# Dyno.net
KiCad netlist of a schematic drawn in EAGLE
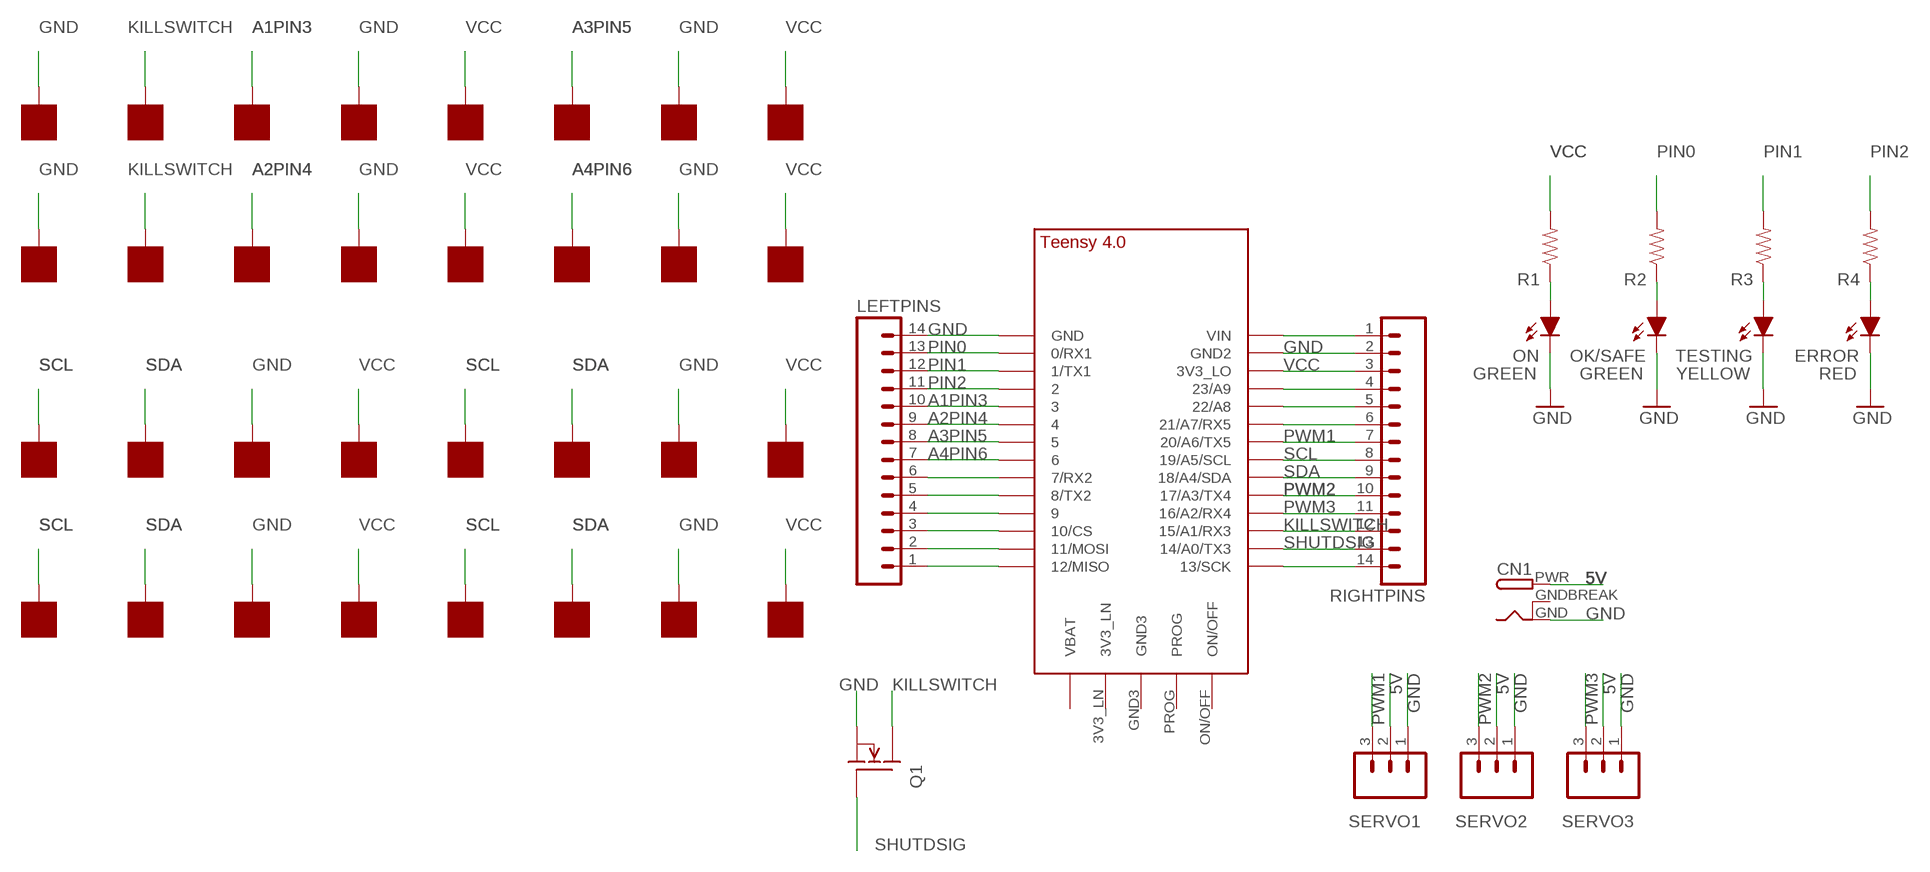
[diagram p0: schematic, sheet 1]

(export (version "E")
  (design (tool "Eeschema 10.0.6"))
  (components
    (comp (ref "A1")
      (value "SOLDER_PAD")
      (footprint "eagle-import:SOLDER_PAD_XSMALL")
      (libsource (lib "eagle-import") (part "SOLDER_PAD"))
    )
    (comp (ref "A1GND")
      (value "SOLDER_PAD")
      (footprint "eagle-import:SOLDER_PAD_XSMALL")
      (libsource (lib "eagle-import") (part "SOLDER_PAD"))
    )
    (comp (ref "A1VCC")
      (value "SOLDER_PAD")
      (footprint "eagle-import:SOLDER_PAD_XSMALL")
      (libsource (lib "eagle-import") (part "SOLDER_PAD"))
    )
    (comp (ref "A2")
      (value "SOLDER_PAD")
      (footprint "eagle-import:SOLDER_PAD_XSMALL")
      (libsource (lib "eagle-import") (part "SOLDER_PAD"))
    )
    (comp (ref "A2GND")
      (value "SOLDER_PAD")
      (footprint "eagle-import:SOLDER_PAD_XSMALL")
      (libsource (lib "eagle-import") (part "SOLDER_PAD"))
    )
    (comp (ref "A2VCC")
      (value "SOLDER_PAD")
      (footprint "eagle-import:SOLDER_PAD_XSMALL")
      (libsource (lib "eagle-import") (part "SOLDER_PAD"))
    )
    (comp (ref "A3")
      (value "SOLDER_PAD")
      (footprint "eagle-import:SOLDER_PAD_XSMALL")
      (libsource (lib "eagle-import") (part "SOLDER_PAD"))
    )
    (comp (ref "A3GND")
      (value "SOLDER_PAD")
      (footprint "eagle-import:SOLDER_PAD_XSMALL")
      (libsource (lib "eagle-import") (part "SOLDER_PAD"))
    )
    (comp (ref "A3VCC")
      (value "SOLDER_PAD")
      (footprint "eagle-import:SOLDER_PAD_XSMALL")
      (libsource (lib "eagle-import") (part "SOLDER_PAD"))
    )
    (comp (ref "A4")
      (value "SOLDER_PAD")
      (footprint "eagle-import:SOLDER_PAD_XSMALL")
      (libsource (lib "eagle-import") (part "SOLDER_PAD"))
    )
    (comp (ref "A4GND")
      (value "SOLDER_PAD")
      (footprint "eagle-import:SOLDER_PAD_XSMALL")
      (libsource (lib "eagle-import") (part "SOLDER_PAD"))
    )
    (comp (ref "A4VCC")
      (value "SOLDER_PAD")
      (footprint "eagle-import:SOLDER_PAD_XSMALL")
      (libsource (lib "eagle-import") (part "SOLDER_PAD"))
    )
    (comp (ref "CN1")
      (value "DCBARRELPTH")
      (footprint "eagle-import:DCJACK_2MM_PTH")
      (libsource (lib "eagle-import") (part "DCBARRELPTH"))
    )
    (comp (ref "EMERGENCYSTOPBUTTON")
      (value "SOLDER_PAD")
      (footprint "eagle-import:SOLDER_PAD_XSMALL")
      (libsource (lib "eagle-import") (part "SOLDER_PAD"))
    )
    (comp (ref "ERROR")
      (value "RED")
      (footprint "eagle-import:LED-5MM")
      (libsource (lib "eagle-import") (part "LED-5MM"))
    )
    (comp (ref "GNDBUTTON")
      (value "SOLDER_PAD")
      (footprint "eagle-import:SOLDER_PAD_XSMALL")
      (libsource (lib "eagle-import") (part "SOLDER_PAD"))
    )
    (comp (ref "GNDKILL")
      (value "SOLDER_PAD")
      (footprint "eagle-import:SOLDER_PAD_XSMALL")
      (libsource (lib "eagle-import") (part "SOLDER_PAD"))
    )
    (comp (ref "I2CGND1")
      (value "SOLDER_PAD")
      (footprint "eagle-import:SOLDER_PAD_XSMALL")
      (libsource (lib "eagle-import") (part "SOLDER_PAD"))
    )
    (comp (ref "I2CGND2")
      (value "SOLDER_PAD")
      (footprint "eagle-import:SOLDER_PAD_XSMALL")
      (libsource (lib "eagle-import") (part "SOLDER_PAD"))
    )
    (comp (ref "I2CGND3")
      (value "SOLDER_PAD")
      (footprint "eagle-import:SOLDER_PAD_XSMALL")
      (libsource (lib "eagle-import") (part "SOLDER_PAD"))
    )
    (comp (ref "I2CGND4")
      (value "SOLDER_PAD")
      (footprint "eagle-import:SOLDER_PAD_XSMALL")
      (libsource (lib "eagle-import") (part "SOLDER_PAD"))
    )
    (comp (ref "I2CVCC1")
      (value "SOLDER_PAD")
      (footprint "eagle-import:SOLDER_PAD_XSMALL")
      (libsource (lib "eagle-import") (part "SOLDER_PAD"))
    )
    (comp (ref "I2CVCC2")
      (value "SOLDER_PAD")
      (footprint "eagle-import:SOLDER_PAD_XSMALL")
      (libsource (lib "eagle-import") (part "SOLDER_PAD"))
    )
    (comp (ref "I2CVCC3")
      (value "SOLDER_PAD")
      (footprint "eagle-import:SOLDER_PAD_XSMALL")
      (libsource (lib "eagle-import") (part "SOLDER_PAD"))
    )
    (comp (ref "I2CVCC4")
      (value "SOLDER_PAD")
      (footprint "eagle-import:SOLDER_PAD_XSMALL")
      (libsource (lib "eagle-import") (part "SOLDER_PAD"))
    )
    (comp (ref "KILLSWITCH")
      (value "SOLDER_PAD")
      (footprint "eagle-import:SOLDER_PAD_XSMALL")
      (libsource (lib "eagle-import") (part "SOLDER_PAD"))
    )
    (comp (ref "LEFTPINS")
      (value "M14")
      (footprint "eagle-import:14P")
      (libsource (lib "eagle-import") (part "M14"))
    )
    (comp (ref "OK/SAFE")
      (value "GREEN")
      (footprint "eagle-import:LED-5MM")
      (libsource (lib "eagle-import") (part "LED-5MM"))
    )
    (comp (ref "ON")
      (value "GREEN")
      (footprint "eagle-import:LED-5MM")
      (libsource (lib "eagle-import") (part "LED-5MM"))
    )
    (comp (ref "Q1")
      (value "DMG3406LSOT")
      (footprint "eagle-import:SOT23")
      (libsource (lib "eagle-import") (part "DMG3406LSOT"))
    )
    (comp (ref "R1")
      (value "RESISTOR0603-RES")
      (footprint "eagle-import:0603-RES")
      (libsource (lib "eagle-import") (part "RESISTOR0603-RES"))
    )
    (comp (ref "R2")
      (value "RESISTOR0603-RES")
      (footprint "eagle-import:0603-RES")
      (libsource (lib "eagle-import") (part "RESISTOR0603-RES"))
    )
    (comp (ref "R3")
      (value "RESISTOR0603-RES")
      (footprint "eagle-import:0603-RES")
      (libsource (lib "eagle-import") (part "RESISTOR0603-RES"))
    )
    (comp (ref "R4")
      (value "RESISTOR0603-RES")
      (footprint "eagle-import:0603-RES")
      (libsource (lib "eagle-import") (part "RESISTOR0603-RES"))
    )
    (comp (ref "RIGHTPINS")
      (value "M14")
      (footprint "eagle-import:14P")
      (libsource (lib "eagle-import") (part "M14"))
    )
    (comp (ref "SCL1")
      (value "SOLDER_PAD")
      (footprint "eagle-import:SOLDER_PAD_XSMALL")
      (libsource (lib "eagle-import") (part "SOLDER_PAD"))
    )
    (comp (ref "SCL2")
      (value "SOLDER_PAD")
      (footprint "eagle-import:SOLDER_PAD_XSMALL")
      (libsource (lib "eagle-import") (part "SOLDER_PAD"))
    )
    (comp (ref "SCL3")
      (value "SOLDER_PAD")
      (footprint "eagle-import:SOLDER_PAD_XSMALL")
      (libsource (lib "eagle-import") (part "SOLDER_PAD"))
    )
    (comp (ref "SCL4")
      (value "SOLDER_PAD")
      (footprint "eagle-import:SOLDER_PAD_XSMALL")
      (libsource (lib "eagle-import") (part "SOLDER_PAD"))
    )
    (comp (ref "SDA1")
      (value "SOLDER_PAD")
      (footprint "eagle-import:SOLDER_PAD_XSMALL")
      (libsource (lib "eagle-import") (part "SOLDER_PAD"))
    )
    (comp (ref "SDA2")
      (value "SOLDER_PAD")
      (footprint "eagle-import:SOLDER_PAD_XSMALL")
      (libsource (lib "eagle-import") (part "SOLDER_PAD"))
    )
    (comp (ref "SDA3")
      (value "SOLDER_PAD")
      (footprint "eagle-import:SOLDER_PAD_XSMALL")
      (libsource (lib "eagle-import") (part "SOLDER_PAD"))
    )
    (comp (ref "SDA4")
      (value "SOLDER_PAD")
      (footprint "eagle-import:SOLDER_PAD_XSMALL")
      (libsource (lib "eagle-import") (part "SOLDER_PAD"))
    )
    (comp (ref "SERVO1")
      (value "M03")
      (footprint "eagle-import:1X03")
      (libsource (lib "eagle-import") (part "M03"))
    )
    (comp (ref "SERVO2")
      (value "M03")
      (footprint "eagle-import:1X03")
      (libsource (lib "eagle-import") (part "M03"))
    )
    (comp (ref "SERVO3")
      (value "M03")
      (footprint "eagle-import:1X03")
      (libsource (lib "eagle-import") (part "M03"))
    )
    (comp (ref "TESTING")
      (value "YELLOW")
      (footprint "eagle-import:LED-5MM")
      (libsource (lib "eagle-import") (part "LED-5MM"))
    )
    (comp (ref "U$1")
      (value "TEENSY_4.0")
      (footprint "eagle-import:TEENSY_4.0")
      (libsource (lib "eagle-import") (part "TEENSY_4.0"))
    )
  )
  (nets
    (net (code "1") (name "/5V") (class "Default")
      (node (ref "CN1") (pin "PWR") (pinfunction "PWR_PWR") (pintype "power_in"))
      (node (ref "SERVO1") (pin "2") (pinfunction "2_2") (pintype "passive"))
      (node (ref "SERVO2") (pin "2") (pinfunction "2_2") (pintype "passive"))
      (node (ref "SERVO3") (pin "2") (pinfunction "2_2") (pintype "passive"))
    )
    (net (code "2") (name "/A1PIN3") (class "Default")
      (node (ref "A1") (pin "P$1") (pinfunction "P$1_P$1") (pintype "bidirectional"))
      (node (ref "LEFTPINS") (pin "10") (pinfunction "10_10") (pintype "passive"))
      (node (ref "U$1") (pin "3/CANTX") (pinfunction "3_3/CANTX") (pintype "bidirectional"))
    )
    (net (code "3") (name "/A2PIN4") (class "Default")
      (node (ref "A2") (pin "P$1") (pinfunction "P$1_P$1") (pintype "bidirectional"))
      (node (ref "LEFTPINS") (pin "9") (pinfunction "9_9") (pintype "passive"))
      (node (ref "U$1") (pin "4/CANRX") (pinfunction "4_4/CANRX") (pintype "bidirectional"))
    )
    (net (code "4") (name "/A3PIN5") (class "Default")
      (node (ref "A3") (pin "P$1") (pinfunction "P$1_P$1") (pintype "bidirectional"))
      (node (ref "LEFTPINS") (pin "8") (pinfunction "8_8") (pintype "passive"))
      (node (ref "U$1") (pin "5") (pinfunction "5_5") (pintype "bidirectional"))
    )
    (net (code "5") (name "/A4PIN6") (class "Default")
      (node (ref "A4") (pin "P$1") (pinfunction "P$1_P$1") (pintype "bidirectional"))
      (node (ref "LEFTPINS") (pin "7") (pinfunction "7_7") (pintype "passive"))
      (node (ref "U$1") (pin "6") (pinfunction "6_6") (pintype "bidirectional"))
    )
    (net (code "6") (name "/GNDBREAK") (class "Default")
      (node (ref "CN1") (pin "GNDBREAK") (pinfunction "GNDBREAK_GNDBREAK") (pintype "power_in"))
    )
    (net (code "7") (name "/KILLSWITCH") (class "Default")
      (node (ref "EMERGENCYSTOPBUTTON") (pin "P$1") (pinfunction "P$1_P$1") (pintype "bidirectional"))
      (node (ref "KILLSWITCH") (pin "P$1") (pinfunction "P$1_P$1") (pintype "bidirectional"))
      (node (ref "Q1") (pin "3") (pinfunction "D_3") (pintype "passive"))
      (node (ref "RIGHTPINS") (pin "12") (pinfunction "12_12") (pintype "passive"))
      (node (ref "U$1") (pin "15/A1") (pinfunction "15/A1/RX3_15/A1") (pintype "bidirectional"))
    )
    (net (code "8") (name "/PIN0") (class "Default")
      (node (ref "LEFTPINS") (pin "13") (pinfunction "13_13") (pintype "passive"))
      (node (ref "R2") (pin "2") (pinfunction "2_2") (pintype "passive"))
      (node (ref "U$1") (pin "0/RX") (pinfunction "0/RX1_0/RX") (pintype "bidirectional"))
    )
    (net (code "9") (name "/PIN1") (class "Default")
      (node (ref "LEFTPINS") (pin "12") (pinfunction "12_12") (pintype "passive"))
      (node (ref "R3") (pin "2") (pinfunction "2_2") (pintype "passive"))
      (node (ref "U$1") (pin "1/TX") (pinfunction "1/TX1_1/TX") (pintype "bidirectional"))
    )
    (net (code "10") (name "/PIN2") (class "Default")
      (node (ref "LEFTPINS") (pin "11") (pinfunction "11_11") (pintype "passive"))
      (node (ref "R4") (pin "2") (pinfunction "2_2") (pintype "passive"))
      (node (ref "U$1") (pin "2") (pinfunction "2_2") (pintype "bidirectional"))
    )
    (net (code "11") (name "/PWM1") (class "Default")
      (node (ref "RIGHTPINS") (pin "7") (pinfunction "7_7") (pintype "passive"))
      (node (ref "SERVO1") (pin "3") (pinfunction "3_3") (pintype "passive"))
      (node (ref "U$1") (pin "20/A6") (pinfunction "20/A6/TX5_20/A6") (pintype "bidirectional"))
    )
    (net (code "12") (name "/PWM2") (class "Default")
      (node (ref "RIGHTPINS") (pin "10") (pinfunction "10_10") (pintype "passive"))
      (node (ref "SERVO2") (pin "3") (pinfunction "3_3") (pintype "passive"))
      (node (ref "U$1") (pin "17/A3") (pinfunction "17/A3/TX4_17/A3") (pintype "bidirectional"))
    )
    (net (code "13") (name "/PWM3") (class "Default")
      (node (ref "RIGHTPINS") (pin "11") (pinfunction "11_11") (pintype "passive"))
      (node (ref "SERVO3") (pin "3") (pinfunction "3_3") (pintype "passive"))
      (node (ref "U$1") (pin "16/A2") (pinfunction "16/A2/RX4_16/A2") (pintype "bidirectional"))
    )
    (net (code "14") (name "/SCL") (class "Default")
      (node (ref "RIGHTPINS") (pin "8") (pinfunction "8_8") (pintype "passive"))
      (node (ref "SCL1") (pin "P$1") (pinfunction "P$1_P$1") (pintype "bidirectional"))
      (node (ref "SCL2") (pin "P$1") (pinfunction "P$1_P$1") (pintype "bidirectional"))
      (node (ref "SCL3") (pin "P$1") (pinfunction "P$1_P$1") (pintype "bidirectional"))
      (node (ref "SCL4") (pin "P$1") (pinfunction "P$1_P$1") (pintype "bidirectional"))
      (node (ref "U$1") (pin "19/A5/SCL") (pinfunction "19/A5/SCL_19/A5/SCL") (pintype "bidirectional"))
    )
    (net (code "15") (name "/SDA") (class "Default")
      (node (ref "RIGHTPINS") (pin "9") (pinfunction "9_9") (pintype "passive"))
      (node (ref "SDA1") (pin "P$1") (pinfunction "P$1_P$1") (pintype "bidirectional"))
      (node (ref "SDA2") (pin "P$1") (pinfunction "P$1_P$1") (pintype "bidirectional"))
      (node (ref "SDA3") (pin "P$1") (pinfunction "P$1_P$1") (pintype "bidirectional"))
      (node (ref "SDA4") (pin "P$1") (pinfunction "P$1_P$1") (pintype "bidirectional"))
      (node (ref "U$1") (pin "18/A4/SDA") (pinfunction "18/A4/SDA_18/A4/SDA") (pintype "bidirectional"))
    )
    (net (code "16") (name "/SHUTDSIG") (class "Default")
      (node (ref "Q1") (pin "1") (pinfunction "G_1") (pintype "passive"))
      (node (ref "RIGHTPINS") (pin "13") (pinfunction "13_13") (pintype "passive"))
      (node (ref "U$1") (pin "14/A0") (pinfunction "14/A0/TX3_14/A0") (pintype "bidirectional"))
    )
    (net (code "17") (name "/VCC") (class "Default")
      (node (ref "A1VCC") (pin "P$1") (pinfunction "P$1_P$1") (pintype "bidirectional"))
      (node (ref "A2VCC") (pin "P$1") (pinfunction "P$1_P$1") (pintype "bidirectional"))
      (node (ref "A3VCC") (pin "P$1") (pinfunction "P$1_P$1") (pintype "bidirectional"))
      (node (ref "A4VCC") (pin "P$1") (pinfunction "P$1_P$1") (pintype "bidirectional"))
      (node (ref "I2CVCC1") (pin "P$1") (pinfunction "P$1_P$1") (pintype "bidirectional"))
      (node (ref "I2CVCC2") (pin "P$1") (pinfunction "P$1_P$1") (pintype "bidirectional"))
      (node (ref "I2CVCC3") (pin "P$1") (pinfunction "P$1_P$1") (pintype "bidirectional"))
      (node (ref "I2CVCC4") (pin "P$1") (pinfunction "P$1_P$1") (pintype "bidirectional"))
      (node (ref "R1") (pin "2") (pinfunction "2_2") (pintype "passive"))
      (node (ref "RIGHTPINS") (pin "3") (pinfunction "3_3") (pintype "passive"))
      (node (ref "U$1") (pin "3V3_LO") (pinfunction "3V3_LO_3V3_LO") (pintype "bidirectional"))
    )
    (net (code "18") (name "GND") (class "Default")
      (node (ref "A1GND") (pin "P$1") (pinfunction "P$1_P$1") (pintype "bidirectional"))
      (node (ref "A2GND") (pin "P$1") (pinfunction "P$1_P$1") (pintype "bidirectional"))
      (node (ref "A3GND") (pin "P$1") (pinfunction "P$1_P$1") (pintype "bidirectional"))
      (node (ref "A4GND") (pin "P$1") (pinfunction "P$1_P$1") (pintype "bidirectional"))
      (node (ref "CN1") (pin "GND") (pinfunction "GND_GND") (pintype "power_in"))
      (node (ref "ERROR") (pin "K") (pinfunction "C_K") (pintype "passive"))
      (node (ref "GNDBUTTON") (pin "P$1") (pinfunction "P$1_P$1") (pintype "bidirectional"))
      (node (ref "GNDKILL") (pin "P$1") (pinfunction "P$1_P$1") (pintype "bidirectional"))
      (node (ref "I2CGND1") (pin "P$1") (pinfunction "P$1_P$1") (pintype "bidirectional"))
      (node (ref "I2CGND2") (pin "P$1") (pinfunction "P$1_P$1") (pintype "bidirectional"))
      (node (ref "I2CGND3") (pin "P$1") (pinfunction "P$1_P$1") (pintype "bidirectional"))
      (node (ref "I2CGND4") (pin "P$1") (pinfunction "P$1_P$1") (pintype "bidirectional"))
      (node (ref "LEFTPINS") (pin "14") (pinfunction "14_14") (pintype "passive"))
      (node (ref "OK/SAFE") (pin "K") (pinfunction "C_K") (pintype "passive"))
      (node (ref "ON") (pin "K") (pinfunction "C_K") (pintype "passive"))
      (node (ref "Q1") (pin "2") (pinfunction "S_2") (pintype "passive"))
      (node (ref "RIGHTPINS") (pin "2") (pinfunction "2_2") (pintype "passive"))
      (node (ref "SERVO1") (pin "1") (pinfunction "1_1") (pintype "passive"))
      (node (ref "SERVO2") (pin "1") (pinfunction "1_1") (pintype "passive"))
      (node (ref "SERVO3") (pin "1") (pinfunction "1_1") (pintype "passive"))
      (node (ref "TESTING") (pin "K") (pinfunction "C_K") (pintype "passive"))
      (node (ref "U$1") (pin "GND") (pinfunction "GND_GND") (pintype "bidirectional"))
      (node (ref "U$1") (pin "GND2") (pinfunction "GND2_GND2") (pintype "bidirectional"))
    )
    (net (code "19") (name "Net-(ERROR-PadA)") (class "Default")
      (node (ref "ERROR") (pin "A") (pinfunction "A_A") (pintype "passive"))
      (node (ref "R4") (pin "1") (pinfunction "1_1") (pintype "passive"))
    )
    (net (code "20") (name "Net-(LEFTPINS-Pad1)") (class "Default")
      (node (ref "LEFTPINS") (pin "1") (pinfunction "1_1") (pintype "passive"))
      (node (ref "U$1") (pin "12/MISO") (pinfunction "12/MISO_12/MISO") (pintype "bidirectional"))
    )
    (net (code "21") (name "Net-(LEFTPINS-Pad2)") (class "Default")
      (node (ref "LEFTPINS") (pin "2") (pinfunction "2_2") (pintype "passive"))
      (node (ref "U$1") (pin "11/MOSI") (pinfunction "11/MOSI_11/MOSI") (pintype "bidirectional"))
    )
    (net (code "22") (name "Net-(LEFTPINS-Pad3)") (class "Default")
      (node (ref "LEFTPINS") (pin "3") (pinfunction "3_3") (pintype "passive"))
      (node (ref "U$1") (pin "10/CS") (pinfunction "10/CS_10/CS") (pintype "bidirectional"))
    )
    (net (code "23") (name "Net-(OK/SAFE-PadA)") (class "Default")
      (node (ref "OK/SAFE") (pin "A") (pinfunction "A_A") (pintype "passive"))
      (node (ref "R2") (pin "1") (pinfunction "1_1") (pintype "passive"))
    )
    (net (code "24") (name "Net-(ON-PadA)") (class "Default")
      (node (ref "ON") (pin "A") (pinfunction "A_A") (pintype "passive"))
      (node (ref "R1") (pin "1") (pinfunction "1_1") (pintype "passive"))
    )
    (net (code "25") (name "Net-(R3-Pad1)") (class "Default")
      (node (ref "R3") (pin "1") (pinfunction "1_1") (pintype "passive"))
      (node (ref "TESTING") (pin "A") (pinfunction "A_A") (pintype "passive"))
    )
    (net (code "26") (name "Net-(RIGHTPINS-Pad1)") (class "Default")
      (node (ref "RIGHTPINS") (pin "1") (pinfunction "1_1") (pintype "passive"))
      (node (ref "U$1") (pin "VIN") (pinfunction "VIN_VIN") (pintype "bidirectional"))
    )
    (net (code "27") (name "Net-(RIGHTPINS-Pad4)") (class "Default")
      (node (ref "RIGHTPINS") (pin "4") (pinfunction "4_4") (pintype "passive"))
      (node (ref "U$1") (pin "23/A9") (pinfunction "23/A9_23/A9") (pintype "bidirectional"))
    )
    (net (code "28") (name "Net-(RIGHTPINS-Pad5)") (class "Default")
      (node (ref "RIGHTPINS") (pin "5") (pinfunction "5_5") (pintype "passive"))
      (node (ref "U$1") (pin "22/A8") (pinfunction "22/A8_22/A8") (pintype "bidirectional"))
    )
    (net (code "29") (name "Net-(RIGHTPINS-Pad14)") (class "Default")
      (node (ref "RIGHTPINS") (pin "14") (pinfunction "14_14") (pintype "passive"))
      (node (ref "U$1") (pin "13/SCK") (pinfunction "13/SCK_13/SCK") (pintype "bidirectional"))
    )
    (net (code "30") (name "Net-(U$1-7{slash}RX2)") (class "Default")
      (node (ref "LEFTPINS") (pin "6") (pinfunction "6_6") (pintype "passive"))
      (node (ref "U$1") (pin "7") (pinfunction "7/RX2_7") (pintype "bidirectional"))
    )
    (net (code "31") (name "Net-(U$1-8{slash}TX2)") (class "Default")
      (node (ref "LEFTPINS") (pin "5") (pinfunction "5_5") (pintype "passive"))
      (node (ref "U$1") (pin "8") (pinfunction "8/TX2_8") (pintype "bidirectional"))
    )
    (net (code "32") (name "Net-(U$1-9)") (class "Default")
      (node (ref "LEFTPINS") (pin "4") (pinfunction "4_4") (pintype "passive"))
      (node (ref "U$1") (pin "9/CS") (pinfunction "9_9/CS") (pintype "bidirectional"))
    )
    (net (code "33") (name "Net-(U$1-21{slash}A7{slash}RX5)") (class "Default")
      (node (ref "RIGHTPINS") (pin "6") (pinfunction "6_6") (pintype "passive"))
      (node (ref "U$1") (pin "21/A7") (pinfunction "21/A7/RX5_21/A7") (pintype "bidirectional"))
    )
    (net (code "34") (name "unconnected-(U$1-Pad3V3_LN)") (class "Default")
      (node (ref "U$1") (pin "3V3_LN") (pinfunction "3V3_LN_3V3_LN") (pintype "bidirectional"))
    )
    (net (code "35") (name "unconnected-(U$1-PadGND3)") (class "Default")
      (node (ref "U$1") (pin "GND3") (pinfunction "GND3_GND3") (pintype "bidirectional"))
    )
    (net (code "36") (name "unconnected-(U$1-PadON{slash}OFF)") (class "Default")
      (node (ref "U$1") (pin "ON/OFF") (pinfunction "ON/OFF_ON/OFF") (pintype "bidirectional"))
    )
    (net (code "37") (name "unconnected-(U$1-PadPROG)") (class "Default")
      (node (ref "U$1") (pin "PROG") (pinfunction "PROG_PROG") (pintype "bidirectional"))
    )
    (net (code "38") (name "unconnected-(U$1-VBAT-PadVBAT\\)") (class "Default")
      (node (ref "U$1") (pin "VBAT\\") (pinfunction "VBAT_VBAT\\") (pintype "bidirectional"))
    )
  )
)
